# Reflow_Oven_Controller_-_Rev_A.net
KiCad netlist of a schematic drawn in Altium Designer
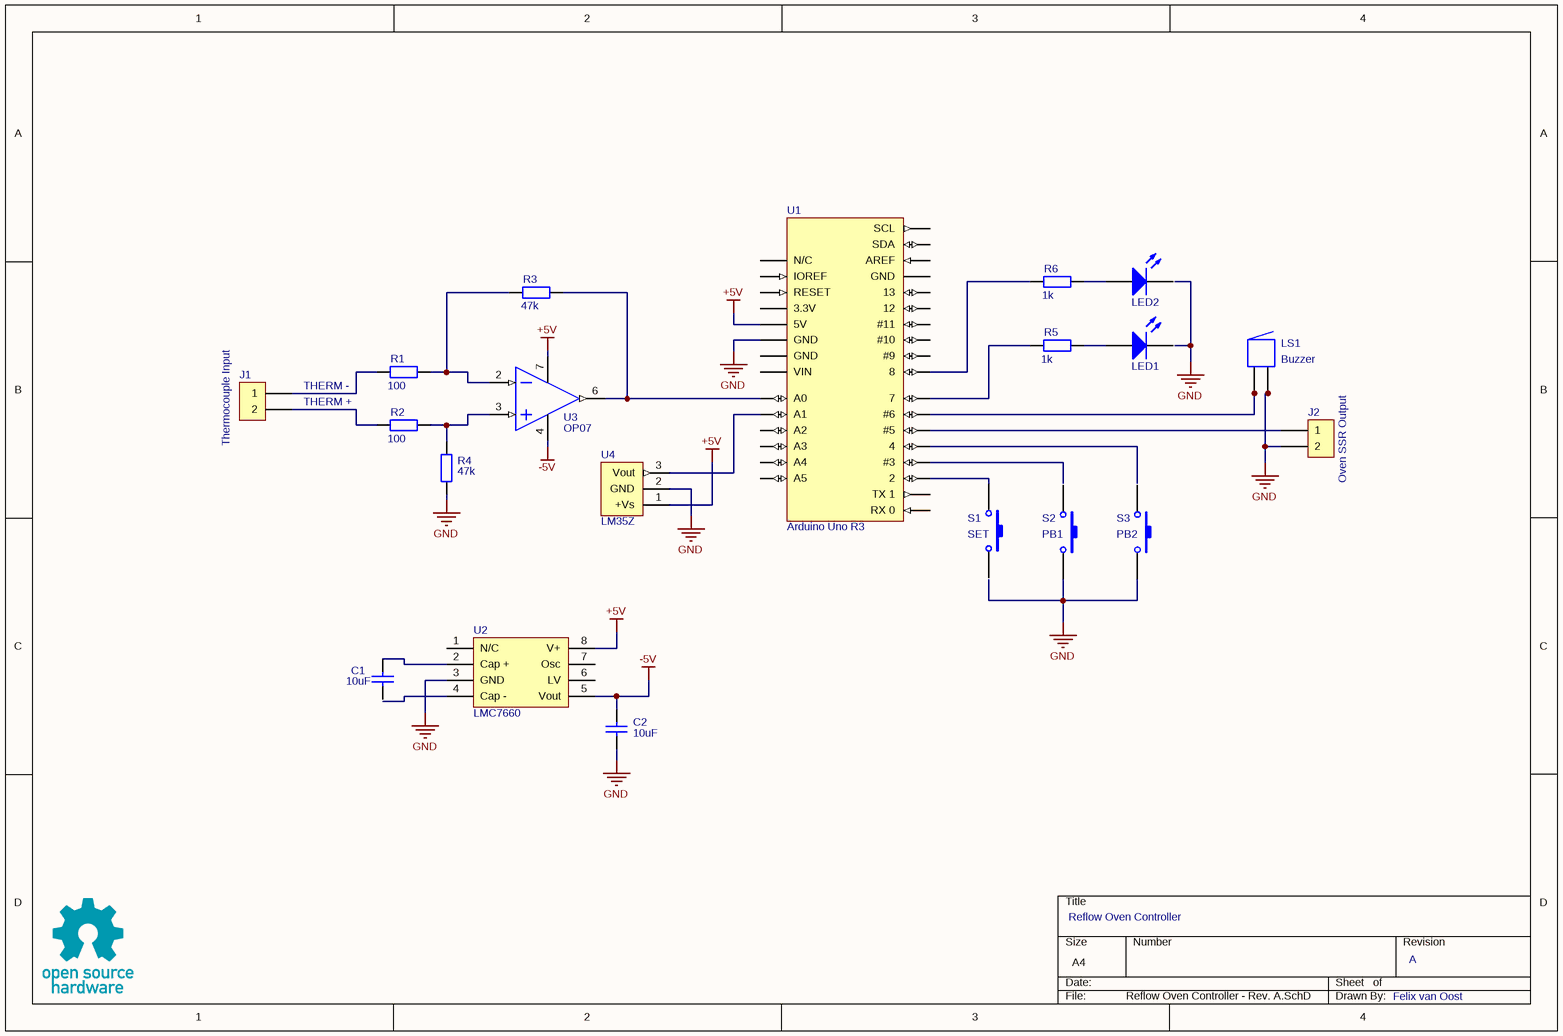
[diagram p0: Reflow Oven Controller - Rev. A.SchDoc]

(export (version "E")
  (design (tool "Eeschema 10.0.6"))
  (components
    (comp (ref "C1")
      (value "10uF")
      (footprint "RAD-0.3")
      (description "Capacitor")
      (fields (field (name "PUBLISHER") "Altium Limited"))
      (libsource (lib "Miscellaneous Devices") (part "Cap"))
    )
    (comp (ref "C2")
      (value "10uF")
      (footprint "RAD-0.3")
      (description "Capacitor")
      (fields (field (name "PUBLISHER") "Altium Limited"))
      (libsource (lib "Miscellaneous Devices") (part "Cap"))
    )
    (comp (ref "D1")
      (value "LED1")
      (footprint "LED-1")
      (description "Typical RED GaAs LED")
      (fields (field (name "PUBLISHER") "Altium Limited"))
      (libsource (lib "Miscellaneous Devices") (part "LED1"))
    )
    (comp (ref "D2")
      (value "LED2")
      (footprint "LED-1")
      (description "Typical RED GaAs LED")
      (fields (field (name "PUBLISHER") "Altium Limited"))
      (libsource (lib "Miscellaneous Devices") (part "LED1"))
    )
    (comp (ref "J1") (value "2-Pin Header") (libsource (lib "") (part "2-Pin Header_1")))
    (comp (ref "J2")
      (value "2-Pin Header")
      (libsource (lib "Reflow Oven Controller - Rev. A") (part "2-Pin Header"))
    )
    (comp (ref "LS1")
      (value "Buzzer")
      (footprint "ABSM-1574")
      (description "Magnetic Transducer Buzzer")
      (fields (field (name "PUBLISHER") "Altium Limited"))
      (libsource (lib "Miscellaneous Devices") (part "Buzzer"))
    )
    (comp (ref "R1")
      (value "100")
      (footprint "AXIAL-0.4")
      (description "Resistor")
      (fields (field (name "PUBLISHER") "Altium Limited"))
      (libsource (lib "Miscellaneous Devices") (part "Res2"))
    )
    (comp (ref "R2")
      (value "100")
      (footprint "AXIAL-0.4")
      (description "Resistor")
      (fields (field (name "PUBLISHER") "Altium Limited"))
      (libsource (lib "Miscellaneous Devices") (part "Res2"))
    )
    (comp (ref "R3")
      (value "47k")
      (footprint "AXIAL-0.4")
      (description "Resistor")
      (fields (field (name "PUBLISHER") "Altium Limited"))
      (libsource (lib "Miscellaneous Devices") (part "Res2"))
    )
    (comp (ref "R4")
      (value "47k")
      (footprint "AXIAL-0.4")
      (description "Resistor")
      (fields (field (name "PUBLISHER") "Altium Limited"))
      (libsource (lib "") (part "Res2_1"))
    )
    (comp (ref "R5")
      (value "1k")
      (footprint "AXIAL-0.4")
      (description "Resistor")
      (fields (field (name "PUBLISHER") "Altium Limited"))
      (libsource (lib "Miscellaneous Devices") (part "Res2"))
    )
    (comp (ref "R6")
      (value "1k")
      (footprint "AXIAL-0.4")
      (description "Resistor")
      (fields (field (name "PUBLISHER") "Altium Limited"))
      (libsource (lib "Miscellaneous Devices") (part "Res2"))
    )
    (comp (ref "S1")
      (value "SET")
      (footprint "SPST-2")
      (description "Switch")
      (fields (field (name "PUBLISHER") "Altium Limited"))
      (libsource (lib "Miscellaneous Devices") (part "SW-PB"))
    )
    (comp (ref "S2")
      (value "PB1")
      (footprint "SPST-2")
      (description "Switch")
      (fields (field (name "PUBLISHER") "Altium Limited"))
      (libsource (lib "Miscellaneous Devices") (part "SW-PB"))
    )
    (comp (ref "S3")
      (value "PB2")
      (footprint "SPST-2")
      (description "Switch")
      (fields (field (name "PUBLISHER") "Altium Limited"))
      (libsource (lib "Miscellaneous Devices") (part "SW-PB"))
    )
    (comp (ref "U1")
      (value "Arduino Uno R3")
      (description "Open-Source Prototyping Plaform")
      (libsource (lib "Reflow Oven Controller - Rev. A") (part "Arduino Uno R3"))
    )
    (comp (ref "U2")
      (value "LMC7660")
      (description "Switched Capacitor Voltage Converter")
      (libsource (lib "Reflow Oven Controller - Rev. A") (part "Texas Instruments LMC7660"))
    )
    (comp (ref "U3")
      (value "OP07")
      (description "Low Offset Op-Amp")
      (libsource (lib "Reflow Oven Controller - Rev. A") (part "Analog Devices OP07"))
    )
    (comp (ref "U4")
      (value "LM35Z")
      (description "Celsius Temperature Sensor (TO-92)")
      (libsource (lib "Reflow Oven Controller - Rev. A") (part "Texas Instruments LM35Z"))
    )
  )
  (nets
    (net (code "1") (name "+5V") (class "Default")
      (node (ref "U1") (pin "5") (pinfunction "5V_5") (pintype "power_in"))
      (node (ref "U2") (pin "8") (pinfunction "V+_8") (pintype "power_in"))
      (node (ref "U3") (pin "7") (pinfunction "V+_7") (pintype "power_in"))
      (node (ref "U4") (pin "1") (pinfunction "+Vs_1") (pintype "power_in"))
    )
    (net (code "2") (name "-5V") (class "Default")
      (node (ref "C2") (pin "2") (pinfunction "2_2") (pintype "passive"))
      (node (ref "U2") (pin "5") (pinfunction "Vout_5") (pintype "power_in"))
      (node (ref "U3") (pin "4") (pinfunction "V-_4") (pintype "power_in"))
    )
    (net (code "3") (name "GND") (class "Default")
      (node (ref "C2") (pin "1") (pinfunction "1_1") (pintype "passive"))
      (node (ref "J2") (pin "2") (pinfunction "2_2") (pintype "passive"))
      (node (ref "LS1") (pin "2") (pinfunction "2_2") (pintype "passive"))
      (node (ref "LS1") (pin "2A") (pinfunction "2A_2A") (pintype "passive"))
      (node (ref "R4") (pin "1") (pinfunction "1_1") (pintype "passive"))
      (node (ref "S2") (pin "2") (pinfunction "2_2") (pintype "passive"))
      (node (ref "S3") (pin "2") (pinfunction "2_2") (pintype "passive"))
      (node (ref "U1") (pin "6") (pinfunction "GND_6") (pintype "power_in"))
      (node (ref "U2") (pin "3") (pinfunction "GND_3") (pintype "power_in"))
      (node (ref "U4") (pin "2") (pinfunction "GND_2") (pintype "power_in"))
    )
    (net (code "4") (name "Net-(D1-A)") (class "Default")
      (node (ref "D1") (pin "1") (pinfunction "A_1") (pintype "passive"))
      (node (ref "R5") (pin "2") (pinfunction "2_2") (pintype "passive"))
    )
    (net (code "5") (name "Net-(D2-A)") (class "Default")
      (node (ref "D2") (pin "1") (pinfunction "A_1") (pintype "passive"))
      (node (ref "R6") (pin "2") (pinfunction "2_2") (pintype "passive"))
    )
    (net (code "6") (name "Net-(J1-Pad1)") (class "Default")
      (node (ref "J1") (pin "1") (pinfunction "1_1") (pintype "passive"))
      (node (ref "R1") (pin "1") (pinfunction "1_1") (pintype "passive"))
    )
    (net (code "7") (name "Net-(J1-Pad2)") (class "Default")
      (node (ref "J1") (pin "2") (pinfunction "2_2") (pintype "passive"))
      (node (ref "R2") (pin "1") (pinfunction "1_1") (pintype "passive"))
    )
    (net (code "8") (name "Net-(U1-#5)") (class "Default")
      (node (ref "J2") (pin "1") (pinfunction "1_1") (pintype "passive"))
      (node (ref "U1") (pin "20") (pinfunction "#5_20") (pintype "bidirectional"))
    )
    (net (code "9") (name "Net-(U1-#6)") (class "Default")
      (node (ref "LS1") (pin "1") (pinfunction "1_1") (pintype "passive"))
      (node (ref "LS1") (pin "1A") (pinfunction "1A_1A") (pintype "passive"))
      (node (ref "U1") (pin "21") (pinfunction "#6_21") (pintype "bidirectional"))
    )
    (net (code "10") (name "Net-(U1-2)") (class "Default")
      (node (ref "S1") (pin "1") (pinfunction "1_1") (pintype "passive"))
      (node (ref "U1") (pin "17") (pinfunction "2_17") (pintype "bidirectional"))
    )
    (net (code "11") (name "Net-(U1-7)") (class "Default")
      (node (ref "R5") (pin "1") (pinfunction "1_1") (pintype "passive"))
      (node (ref "U1") (pin "22") (pinfunction "7_22") (pintype "bidirectional"))
    )
    (net (code "12") (name "Net-(U1-8)") (class "Default")
      (node (ref "R6") (pin "1") (pinfunction "1_1") (pintype "passive"))
      (node (ref "U1") (pin "23") (pinfunction "8_23") (pintype "bidirectional"))
    )
    (net (code "13") (name "Net-(U1-A0)") (class "Default")
      (node (ref "R3") (pin "2") (pinfunction "2_2") (pintype "passive"))
      (node (ref "U1") (pin "9") (pinfunction "A0_9") (pintype "bidirectional"))
      (node (ref "U3") (pin "6") (pinfunction "OUT_6") (pintype "output"))
    )
    (net (code "14") (name "Net-(U1-A1)") (class "Default")
      (node (ref "U1") (pin "10") (pinfunction "A1_10") (pintype "bidirectional"))
      (node (ref "U4") (pin "3") (pinfunction "Vout_3") (pintype "output"))
    )
    (net (code "15") (name "Net-(U2-Cap_+)") (class "Default")
      (node (ref "C1") (pin "2") (pinfunction "2_2") (pintype "passive"))
      (node (ref "U2") (pin "2") (pinfunction "Cap_+_2") (pintype "passive"))
    )
    (net (code "16") (name "Net-(U3-+In)") (class "Default")
      (node (ref "R2") (pin "2") (pinfunction "2_2") (pintype "passive"))
      (node (ref "R4") (pin "2") (pinfunction "2_2") (pintype "passive"))
      (node (ref "U3") (pin "3") (pinfunction "+In_3") (pintype "input"))
    )
    (net (code "17") (name "Net-(U3--In)") (class "Default")
      (node (ref "R1") (pin "2") (pinfunction "2_2") (pintype "passive"))
      (node (ref "R3") (pin "1") (pinfunction "1_1") (pintype "passive"))
      (node (ref "U3") (pin "2") (pinfunction "-In_2") (pintype "input"))
    )
    (net (code "18") (name "unconnected-(C1-Pad1)") (class "Default")
      (node (ref "C1") (pin "1") (pinfunction "1_1") (pintype "passive"))
    )
    (net (code "19") (name "unconnected-(D1-K-Pad2)") (class "Default")
      (node (ref "D1") (pin "2") (pinfunction "K_2") (pintype "passive"))
    )
    (net (code "20") (name "unconnected-(D2-K-Pad2)") (class "Default")
      (node (ref "D2") (pin "2") (pinfunction "K_2") (pintype "passive"))
    )
    (net (code "21") (name "unconnected-(S1-Pad2)") (class "Default")
      (node (ref "S1") (pin "2") (pinfunction "2_2") (pintype "passive"))
    )
    (net (code "22") (name "unconnected-(S2-Pad1)") (class "Default")
      (node (ref "S2") (pin "1") (pinfunction "1_1") (pintype "passive"))
    )
    (net (code "23") (name "unconnected-(S3-Pad1)") (class "Default")
      (node (ref "S3") (pin "1") (pinfunction "1_1") (pintype "passive"))
    )
    (net (code "24") (name "unconnected-(U1-#3-Pad18)") (class "Default")
      (node (ref "U1") (pin "18") (pinfunction "#3_18") (pintype "bidirectional"))
    )
    (net (code "25") (name "unconnected-(U1-#9-Pad24)") (class "Default")
      (node (ref "U1") (pin "24") (pinfunction "#9_24") (pintype "bidirectional"))
    )
    (net (code "26") (name "unconnected-(U1-#10-Pad25)") (class "Default")
      (node (ref "U1") (pin "25") (pinfunction "#10_25") (pintype "bidirectional"))
    )
    (net (code "27") (name "unconnected-(U1-#11-Pad26)") (class "Default")
      (node (ref "U1") (pin "26") (pinfunction "#11_26") (pintype "bidirectional"))
    )
    (net (code "28") (name "unconnected-(U1-3.3V-Pad4)") (class "Default")
      (node (ref "U1") (pin "4") (pinfunction "3.3V_4") (pintype "power_in"))
    )
    (net (code "29") (name "unconnected-(U1-4-Pad19)") (class "Default")
      (node (ref "U1") (pin "19") (pinfunction "4_19") (pintype "bidirectional"))
    )
    (net (code "30") (name "unconnected-(U1-12-Pad27)") (class "Default")
      (node (ref "U1") (pin "27") (pinfunction "12_27") (pintype "bidirectional"))
    )
    (net (code "31") (name "unconnected-(U1-13-Pad28)") (class "Default")
      (node (ref "U1") (pin "28") (pinfunction "13_28") (pintype "bidirectional"))
    )
    (net (code "32") (name "unconnected-(U1-A2-Pad11)") (class "Default")
      (node (ref "U1") (pin "11") (pinfunction "A2_11") (pintype "bidirectional"))
    )
    (net (code "33") (name "unconnected-(U1-A3-Pad12)") (class "Default")
      (node (ref "U1") (pin "12") (pinfunction "A3_12") (pintype "bidirectional"))
    )
    (net (code "34") (name "unconnected-(U1-A4-Pad13)") (class "Default")
      (node (ref "U1") (pin "13") (pinfunction "A4_13") (pintype "bidirectional"))
    )
    (net (code "35") (name "unconnected-(U1-A5-Pad14)") (class "Default")
      (node (ref "U1") (pin "14") (pinfunction "A5_14") (pintype "bidirectional"))
    )
    (net (code "36") (name "unconnected-(U1-AREF-Pad28)") (class "Default")
      (node (ref "U1") (pin "28") (pinfunction "AREF_28") (pintype "input"))
    )
    (net (code "37") (name "unconnected-(U1-GND-Pad7)") (class "Default")
      (node (ref "U1") (pin "7") (pinfunction "GND_7") (pintype "power_in"))
    )
    (net (code "38") (name "unconnected-(U1-GND-Pad28)") (class "Default")
      (node (ref "U1") (pin "28") (pinfunction "GND_28") (pintype "power_in"))
    )
    (net (code "39") (name "unconnected-(U1-IOREF-Pad2)") (class "Default")
      (node (ref "U1") (pin "2") (pinfunction "IOREF_2") (pintype "input"))
    )
    (net (code "40") (name "unconnected-(U1-N{slash}C-Pad1)") (class "Default")
      (node (ref "U1") (pin "1") (pinfunction "N/C_1") (pintype "passive"))
    )
    (net (code "41") (name "unconnected-(U1-RESET-Pad3)") (class "Default")
      (node (ref "U1") (pin "3") (pinfunction "RESET_3") (pintype "input"))
    )
    (net (code "42") (name "unconnected-(U1-RX_0-Pad15)") (class "Default")
      (node (ref "U1") (pin "15") (pinfunction "RX_0_15") (pintype "input"))
    )
    (net (code "43") (name "unconnected-(U1-SCL-Pad29)") (class "Default")
      (node (ref "U1") (pin "29") (pinfunction "SCL_29") (pintype "output"))
    )
    (net (code "44") (name "unconnected-(U1-SDA-Pad28)") (class "Default")
      (node (ref "U1") (pin "28") (pinfunction "SDA_28") (pintype "bidirectional"))
    )
    (net (code "45") (name "unconnected-(U1-TX_1-Pad16)") (class "Default")
      (node (ref "U1") (pin "16") (pinfunction "TX_1_16") (pintype "output"))
    )
    (net (code "46") (name "unconnected-(U1-VIN-Pad8)") (class "Default")
      (node (ref "U1") (pin "8") (pinfunction "VIN_8") (pintype "power_in"))
    )
    (net (code "47") (name "unconnected-(U2-Cap_--Pad4)") (class "Default")
      (node (ref "U2") (pin "4") (pinfunction "Cap_-_4") (pintype "passive"))
    )
    (net (code "48") (name "unconnected-(U2-LV-Pad6)") (class "Default")
      (node (ref "U2") (pin "6") (pinfunction "LV_6") (pintype "passive"))
    )
    (net (code "49") (name "unconnected-(U2-N{slash}C-Pad1)") (class "Default")
      (node (ref "U2") (pin "1") (pinfunction "N/C_1") (pintype "passive"))
    )
    (net (code "50") (name "unconnected-(U2-Osc-Pad7)") (class "Default")
      (node (ref "U2") (pin "7") (pinfunction "Osc_7") (pintype "passive"))
    )
  )
)
